# design.net
KiCad netlist of a schematic drawn in Altium Designer
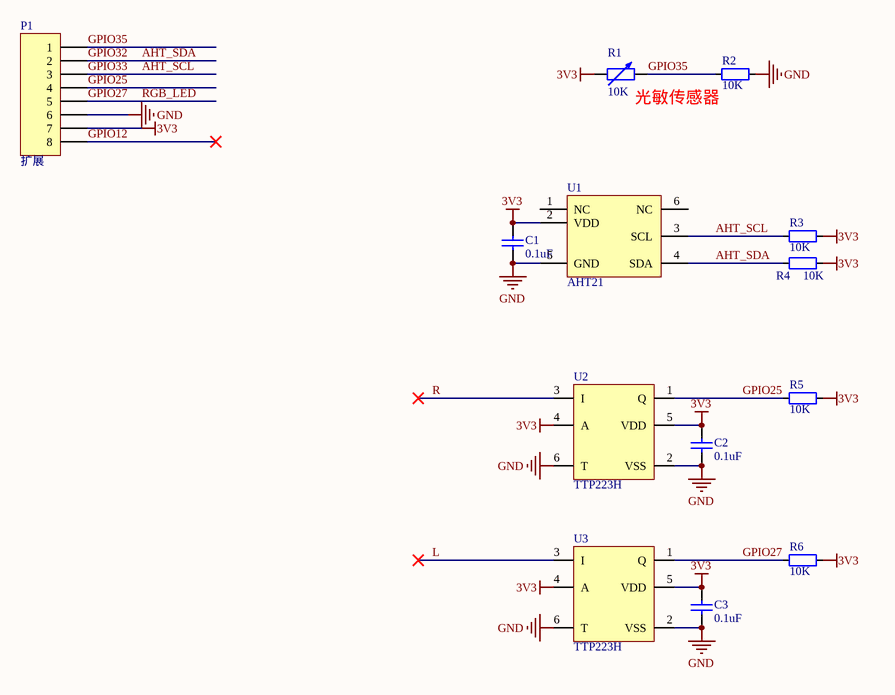
[diagram p0: 触摸扩展板.SchDoc]

(export (version "E")
  (design (tool "Eeschema 10.0.6"))
  (components
    (comp (ref "C1")
      (value "0.1uF")
      (footprint "C_0603")
      (description "Capacitor")
      (fields (field (name "PUBLISHER") "Altium Limited"))
      (libsource (lib "Miscellaneous Devices") (part "Cap"))
    )
    (comp (ref "C2")
      (value "0.1uF")
      (footprint "C_0603")
      (description "Capacitor")
      (fields (field (name "PUBLISHER") "Altium Limited"))
      (libsource (lib "Miscellaneous Devices") (part "Cap"))
    )
    (comp (ref "C3")
      (value "0.1uF")
      (footprint "C_0603")
      (description "Capacitor")
      (fields (field (name "PUBLISHER") "Altium Limited"))
      (libsource (lib "Miscellaneous Devices") (part "Cap"))
    )
    (comp (ref "P1")
      (value "扩展")
      (footprint "FPC0.5 2H-WS-8P")
      (description "Header, 8-Pin")
      (fields (field (name "PUBLISHER") "Altium Limited"))
      (libsource (lib "Miscellaneous Connectors") (part "Header 8"))
    )
    (comp (ref "R1")
      (value "10K")
      (footprint "C_1210")
      (description "Variable Resistor")
      (fields (field (name "PUBLISHER") "Altium Limited"))
      (libsource (lib "Miscellaneous Devices") (part "Res Adj2"))
    )
    (comp (ref "R2")
      (value "10K")
      (footprint "R_0603")
      (description "Resistor")
      (libsource (lib "MyPcbLib") (part "电阻-0402"))
    )
    (comp (ref "R3")
      (value "10K")
      (footprint "R_0603")
      (description "Resistor")
      (libsource (lib "MyPcbLib") (part "电阻-0402"))
    )
    (comp (ref "R4")
      (value "10K")
      (footprint "R_0603")
      (description "Resistor")
      (libsource (lib "MyPcbLib") (part "电阻-0402"))
    )
    (comp (ref "R5")
      (value "10K")
      (footprint "R_0603")
      (description "Resistor")
      (libsource (lib "MyPcbLib") (part "电阻-0402"))
    )
    (comp (ref "R6")
      (value "10K")
      (footprint "R_0603")
      (description "Resistor")
      (libsource (lib "MyPcbLib") (part "电阻-0402"))
    )
    (comp (ref "U1")
      (value "AHT21")
      (footprint "AHT21")
      (description "温湿度传感器")
      (libsource (lib "Misaka") (part "AHT21"))
    )
    (comp (ref "U2")
      (value "TTP223H")
      (footprint "SOT23-6-Y")
      (description "触摸传感器")
      (libsource (lib "Misaka") (part "TTP223H"))
    )
    (comp (ref "U3")
      (value "TTP223H")
      (footprint "SOT23-6-Y")
      (description "触摸传感器")
      (libsource (lib "Misaka") (part "TTP223H"))
    )
  )
  (nets
    (net (code "1") (name "/AHT_SCL") (class "Default")
      (node (ref "P1") (pin "3") (pinfunction "3_3") (pintype "passive"))
      (node (ref "R3") (pin "2") (pinfunction "2_2") (pintype "passive"))
      (node (ref "U1") (pin "3") (pinfunction "SCL_3") (pintype "passive"))
    )
    (net (code "2") (name "/AHT_SDA") (class "Default")
      (node (ref "P1") (pin "2") (pinfunction "2_2") (pintype "passive"))
      (node (ref "R4") (pin "2") (pinfunction "2_2") (pintype "passive"))
      (node (ref "U1") (pin "4") (pinfunction "SDA_4") (pintype "passive"))
    )
    (net (code "3") (name "/GPIO12") (class "Default")
      (node (ref "P1") (pin "8") (pinfunction "8_8") (pintype "passive+no_connect"))
    )
    (net (code "4") (name "/GPIO25") (class "Default")
      (node (ref "P1") (pin "4") (pinfunction "4_4") (pintype "passive"))
      (node (ref "R5") (pin "2") (pinfunction "2_2") (pintype "passive"))
      (node (ref "U2") (pin "1") (pinfunction "Q_1") (pintype "passive"))
    )
    (net (code "5") (name "/GPIO27") (class "Default")
      (node (ref "P1") (pin "5") (pinfunction "5_5") (pintype "passive"))
      (node (ref "R6") (pin "2") (pinfunction "2_2") (pintype "passive"))
      (node (ref "U3") (pin "1") (pinfunction "Q_1") (pintype "passive"))
    )
    (net (code "6") (name "/GPIO35") (class "Default")
      (node (ref "P1") (pin "1") (pinfunction "1_1") (pintype "passive"))
      (node (ref "R1") (pin "2") (pinfunction "2_2") (pintype "passive"))
      (node (ref "R2") (pin "2") (pinfunction "2_2") (pintype "passive"))
    )
    (net (code "7") (name "/L") (class "Default")
      (node (ref "U3") (pin "3") (pinfunction "I_3") (pintype "passive+no_connect"))
    )
    (net (code "8") (name "/R") (class "Default")
      (node (ref "U2") (pin "3") (pinfunction "I_3") (pintype "passive+no_connect"))
    )
    (net (code "9") (name "3V3") (class "Default")
      (node (ref "C1") (pin "1") (pinfunction "1_1") (pintype "passive"))
      (node (ref "C2") (pin "1") (pinfunction "1_1") (pintype "passive"))
      (node (ref "C3") (pin "1") (pinfunction "1_1") (pintype "passive"))
      (node (ref "P1") (pin "7") (pinfunction "7_7") (pintype "passive"))
      (node (ref "R1") (pin "1") (pinfunction "1_1") (pintype "passive"))
      (node (ref "R3") (pin "1") (pinfunction "1_1") (pintype "passive"))
      (node (ref "R4") (pin "1") (pinfunction "1_1") (pintype "passive"))
      (node (ref "R5") (pin "1") (pinfunction "1_1") (pintype "passive"))
      (node (ref "R6") (pin "1") (pinfunction "1_1") (pintype "passive"))
      (node (ref "U1") (pin "2") (pinfunction "VDD_2") (pintype "passive"))
      (node (ref "U2") (pin "4") (pinfunction "A_4") (pintype "passive"))
      (node (ref "U2") (pin "5") (pinfunction "VDD_5") (pintype "passive"))
      (node (ref "U3") (pin "4") (pinfunction "A_4") (pintype "passive"))
      (node (ref "U3") (pin "5") (pinfunction "VDD_5") (pintype "passive"))
    )
    (net (code "10") (name "GND") (class "Default")
      (node (ref "C1") (pin "2") (pinfunction "2_2") (pintype "passive"))
      (node (ref "C2") (pin "2") (pinfunction "2_2") (pintype "passive"))
      (node (ref "C3") (pin "2") (pinfunction "2_2") (pintype "passive"))
      (node (ref "P1") (pin "6") (pinfunction "6_6") (pintype "passive"))
      (node (ref "R2") (pin "1") (pinfunction "1_1") (pintype "passive"))
      (node (ref "U1") (pin "5") (pinfunction "GND_5") (pintype "passive"))
      (node (ref "U2") (pin "2") (pinfunction "VSS_2") (pintype "passive"))
      (node (ref "U2") (pin "6") (pinfunction "T_6") (pintype "passive"))
      (node (ref "U3") (pin "2") (pinfunction "VSS_2") (pintype "passive"))
      (node (ref "U3") (pin "6") (pinfunction "T_6") (pintype "passive"))
    )
    (net (code "11") (name "unconnected-(U1-NC-Pad1)") (class "Default")
      (node (ref "U1") (pin "1") (pinfunction "NC_1") (pintype "passive"))
    )
    (net (code "12") (name "unconnected-(U1-NC-Pad6)") (class "Default")
      (node (ref "U1") (pin "6") (pinfunction "NC_6") (pintype "passive"))
    )
  )
)
